# ir-sensor-breakout-mk-2_2-pth.net
KiCad netlist of a schematic drawn in EAGLE
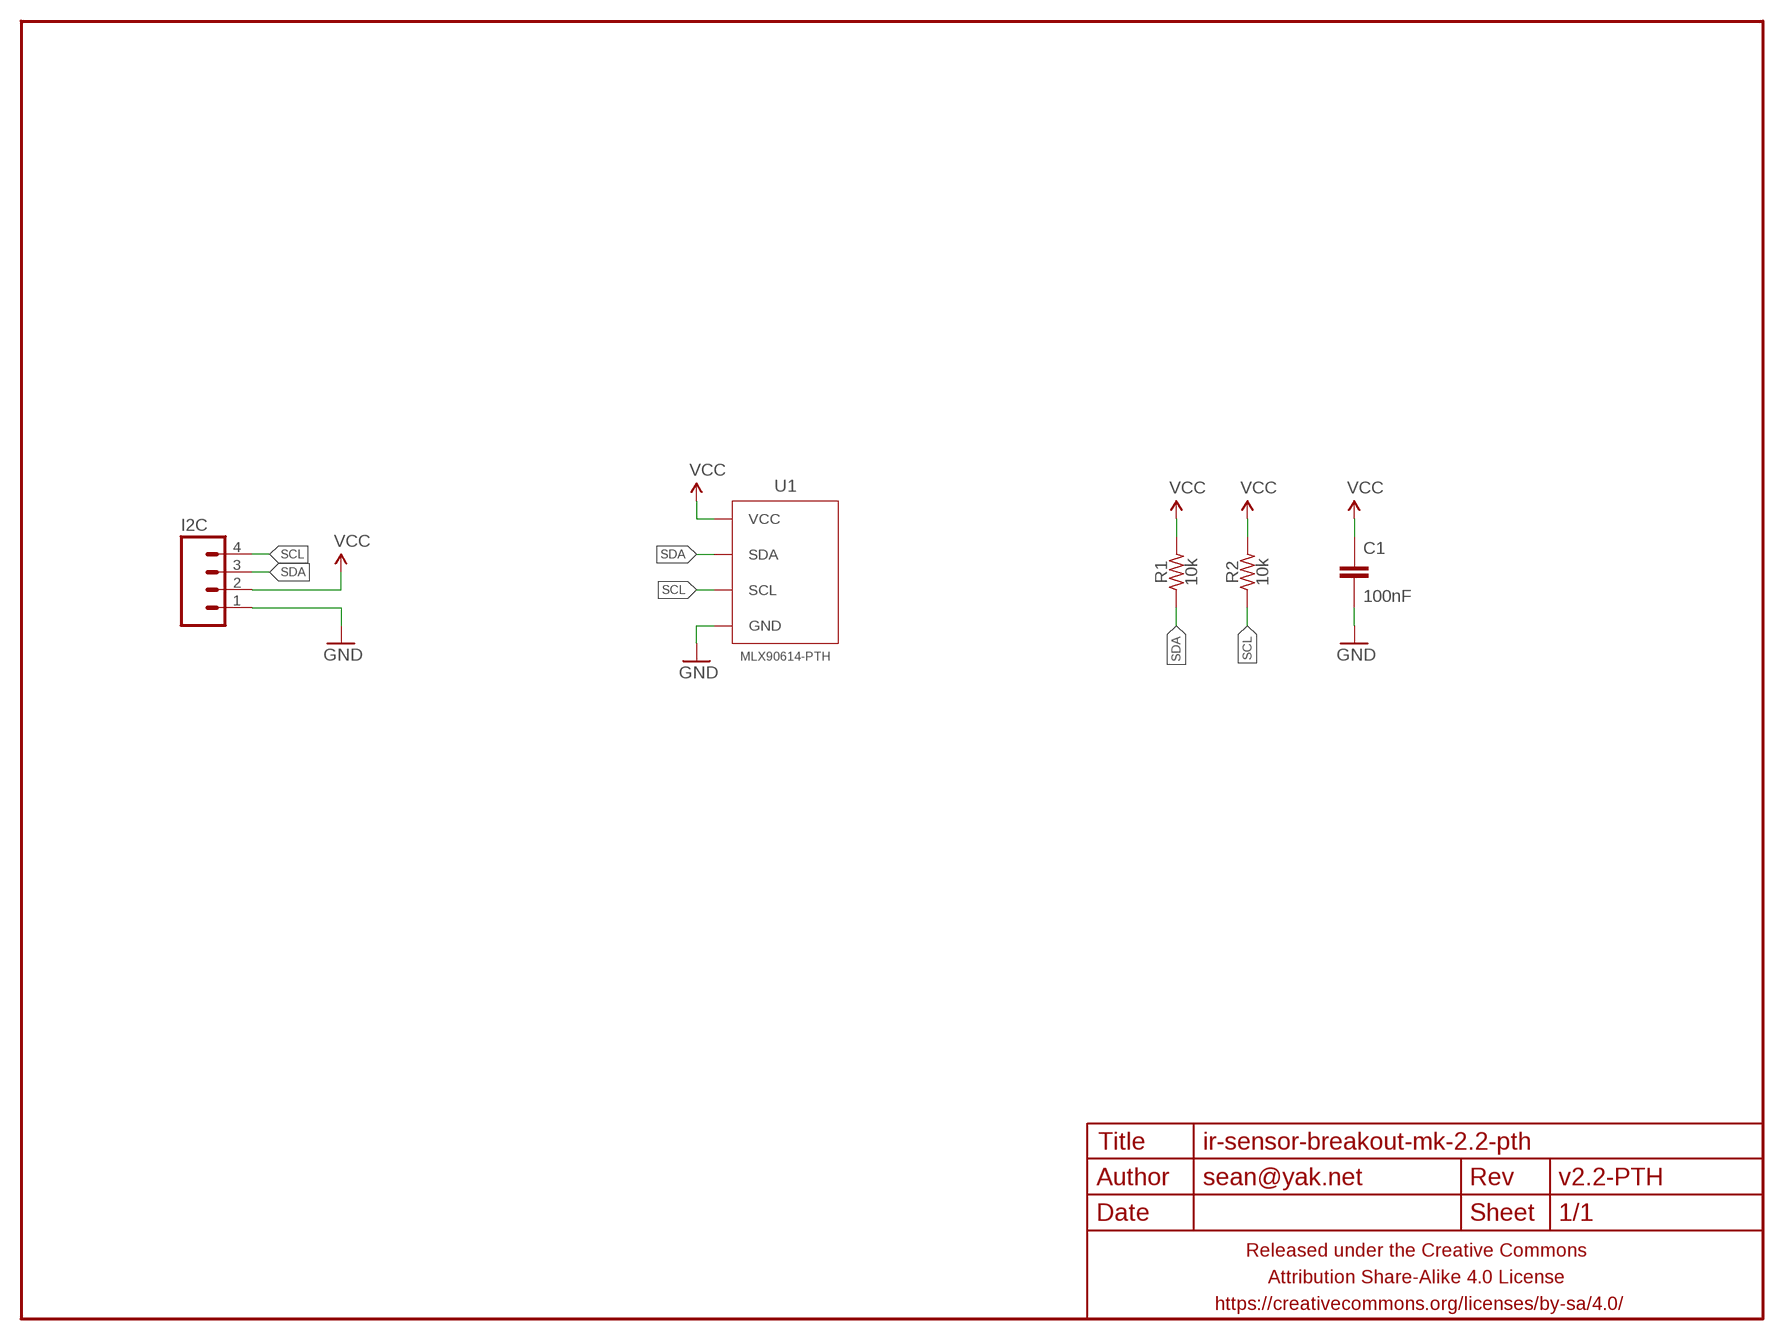
[diagram p0: schematic, sheet 1]

(export (version "E")
  (design (tool "Eeschema 10.0.6"))
  (components
    (comp (ref "C1")
      (value "100nF")
      (footprint "eagle-import:C025-024X044")
      (libsource (lib "eagle-import") (part "CAPACITOR-CERAMIC025-024X044"))
    )
    (comp (ref "FRAME1")
      (value "FRAME-LETTERNO_PACKAGE")
      (footprint "eagle-import:DUMMY")
      (fields (field (name "DESIGNER") "sean@yak.net") (field (name "VERSION") "v2.2-PTH"))
      (libsource (lib "eagle-import") (part "FRAME-LETTERNO_PACKAGE"))
    )
    (comp (ref "I2C")
      (value "M04JST-PTH-VERT")
      (footprint "eagle-import:JST-4-PH-VERT-PTH")
      (libsource (lib "eagle-import") (part "M04JST-PTH-VERT"))
    )
    (comp (ref "R1")
      (value "10k")
      (footprint "eagle-import:RESISTOR-AXIAL-PTH-6.35MM")
      (libsource (lib "eagle-import") (part "RESISTORPTH-AXIAL-6.35MM"))
    )
    (comp (ref "R2")
      (value "10k")
      (footprint "eagle-import:RESISTOR-AXIAL-PTH-6.35MM")
      (libsource (lib "eagle-import") (part "RESISTORPTH-AXIAL-6.35MM"))
    )
    (comp (ref "U1")
      (value "MLX90614-PTH")
      (footprint "eagle-import:TO-39-4")
      (libsource (lib "eagle-import") (part "MLX906145V-PTH"))
    )
  )
  (nets
    (net (code "1") (name "GND") (class "Default")
      (node (ref "C1") (pin "2") (pinfunction "2_2") (pintype "passive"))
      (node (ref "I2C") (pin "1") (pinfunction "1_1") (pintype "passive"))
      (node (ref "U1") (pin "4") (pinfunction "GND_4") (pintype "bidirectional"))
    )
    (net (code "2") (name "SCL") (class "Default")
      (node (ref "I2C") (pin "4") (pinfunction "4_4") (pintype "passive"))
      (node (ref "R2") (pin "P$1") (pinfunction "1_P$1") (pintype "passive"))
      (node (ref "U1") (pin "1") (pinfunction "SCL_1") (pintype "bidirectional"))
    )
    (net (code "3") (name "SDA") (class "Default")
      (node (ref "I2C") (pin "3") (pinfunction "3_3") (pintype "passive"))
      (node (ref "R1") (pin "P$1") (pinfunction "1_P$1") (pintype "passive"))
      (node (ref "U1") (pin "2") (pinfunction "SDA_2") (pintype "bidirectional"))
    )
    (net (code "4") (name "VCC") (class "Default")
      (node (ref "C1") (pin "1") (pinfunction "1_1") (pintype "passive"))
      (node (ref "I2C") (pin "2") (pinfunction "2_2") (pintype "passive"))
      (node (ref "R1") (pin "P$2") (pinfunction "2_P$2") (pintype "passive"))
      (node (ref "R2") (pin "P$2") (pinfunction "2_P$2") (pintype "passive"))
      (node (ref "U1") (pin "3") (pinfunction "VCC_3") (pintype "bidirectional"))
    )
  )
)
